# PidiBoy.net
KiCad netlist of a schematic drawn in EAGLE
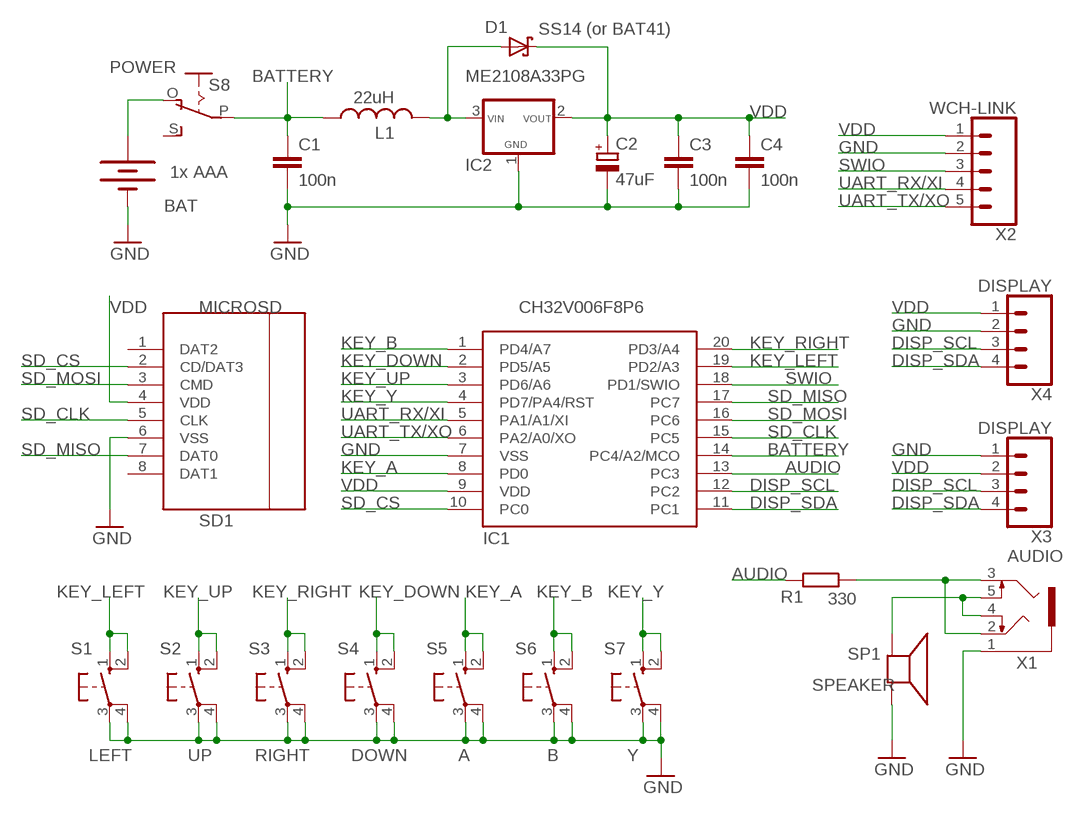
[diagram p0: schematic, sheet 1]

(export (version "E")
  (design (tool "Eeschema 10.0.6"))
  (components
    (comp (ref "BAT")
      (value "1x AAA")
      (footprint "eagle-import:BATTERY-AAA-KIT")
      (libsource (lib "eagle-import") (part "BATTERY-AAA_KIT"))
    )
    (comp (ref "C1")
      (value "100n")
      (footprint "eagle-import:C050-024X044")
      (libsource (lib "eagle-import") (part "C-EU050-024X044"))
    )
    (comp (ref "C2")
      (value "47uF")
      (footprint "eagle-import:E2-5")
      (libsource (lib "eagle-import") (part "CPOL-EUE2-5"))
    )
    (comp (ref "C3")
      (value "100n")
      (footprint "eagle-import:C050-024X044")
      (libsource (lib "eagle-import") (part "C-EU050-024X044"))
    )
    (comp (ref "C4")
      (value "100n")
      (footprint "eagle-import:C050-024X044")
      (libsource (lib "eagle-import") (part "C-EU050-024X044"))
    )
    (comp (ref "D1")
      (value "SS14 (or BAT41)")
      (footprint "eagle-import:DO35-7")
      (libsource (lib "eagle-import") (part "SCHOTTKY-DIODEDO35-7"))
    )
    (comp (ref "IC1")
      (value "CH32V006F8P6")
      (footprint "eagle-import:TSSOP20")
      (libsource (lib "eagle-import") (part "CH32V006F8P6"))
    )
    (comp (ref "IC2")
      (value "ME2108A33PG")
      (footprint "eagle-import:SOT89-R")
      (libsource (lib "eagle-import") (part "ME2108A33PG"))
    )
    (comp (ref "L1")
      (value "22uH")
      (footprint "eagle-import:POWER-CHOKE_WE-TPC")
      (libsource (lib "eagle-import") (part "L-USWE-TPC"))
    )
    (comp (ref "R1")
      (value "330")
      (footprint "eagle-import:0204_7")
      (libsource (lib "eagle-import") (part "R-EU_0204/7"))
    )
    (comp (ref "S1")
      (value "LEFT")
      (footprint "eagle-import:B3F-10XX")
      (fields (field (name "MPN") "B3F-1000"))
      (libsource (lib "eagle-import") (part "10-XX"))
    )
    (comp (ref "S2")
      (value "UP")
      (footprint "eagle-import:B3F-10XX")
      (fields (field (name "MPN") "B3F-1000"))
      (libsource (lib "eagle-import") (part "10-XX"))
    )
    (comp (ref "S3")
      (value "RIGHT")
      (footprint "eagle-import:B3F-10XX")
      (fields (field (name "MPN") "B3F-1000"))
      (libsource (lib "eagle-import") (part "10-XX"))
    )
    (comp (ref "S4")
      (value "DOWN")
      (footprint "eagle-import:B3F-10XX")
      (fields (field (name "MPN") "B3F-1000"))
      (libsource (lib "eagle-import") (part "10-XX"))
    )
    (comp (ref "S5")
      (value "A")
      (footprint "eagle-import:B3F-10XX")
      (fields (field (name "MPN") "B3F-1000"))
      (libsource (lib "eagle-import") (part "10-XX"))
    )
    (comp (ref "S6")
      (value "B")
      (footprint "eagle-import:B3F-10XX")
      (fields (field (name "MPN") "B3F-1000"))
      (libsource (lib "eagle-import") (part "10-XX"))
    )
    (comp (ref "S7")
      (value "Y")
      (footprint "eagle-import:B3F-10XX")
      (fields (field (name "MPN") "B3F-1000"))
      (libsource (lib "eagle-import") (part "10-XX"))
    )
    (comp (ref "S8")
      (value "POWER")
      (footprint "eagle-import:EG1218")
      (libsource (lib "eagle-import") (part "EG1218S"))
    )
    (comp (ref "SD1")
      (value "MICROSD")
      (footprint "eagle-import:MICROSD")
      (libsource (lib "eagle-import") (part "MICROSD"))
    )
    (comp (ref "SP1")
      (value "SPEAKER")
      (footprint "eagle-import:AL60P")
      (libsource (lib "eagle-import") (part "SPEAKER/AL60P"))
    )
    (comp (ref "X1")
      (value "AUDIO")
      (footprint "eagle-import:1503_09")
      (libsource (lib "eagle-import") (part "1503_09"))
    )
    (comp (ref "X2")
      (value "WCH-LINK")
      (footprint "eagle-import:1X05_LONGPADS")
      (libsource (lib "eagle-import") (part "CONN_05PTH_LONGPADS"))
    )
    (comp (ref "X3")
      (value "DISPLAY")
      (footprint "eagle-import:1X04")
      (libsource (lib "eagle-import") (part "CONN_04"))
    )
    (comp (ref "X4")
      (value "DISPLAY")
      (footprint "eagle-import:1X04")
      (libsource (lib "eagle-import") (part "CONN_04"))
    )
  )
  (nets
    (net (code "1") (name "/AUDIO") (class "Default")
      (node (ref "IC1") (pin "13") (pinfunction "PC3_13") (pintype "bidirectional"))
      (node (ref "R1") (pin "2") (pinfunction "2_2") (pintype "passive"))
    )
    (net (code "2") (name "/BATTERY") (class "Default")
      (node (ref "C1") (pin "1") (pinfunction "1_1") (pintype "passive"))
      (node (ref "IC1") (pin "14") (pinfunction "PC4/A2/MCO_14") (pintype "bidirectional"))
      (node (ref "L1") (pin "1") (pinfunction "1_1") (pintype "passive"))
      (node (ref "S8") (pin "P") (pinfunction "P_P") (pintype "passive"))
    )
    (net (code "3") (name "/DISP_SCL") (class "Default")
      (node (ref "IC1") (pin "12") (pinfunction "PC2_12") (pintype "bidirectional"))
      (node (ref "X3") (pin "3") (pinfunction "3_3") (pintype "passive"))
      (node (ref "X4") (pin "3") (pinfunction "3_3") (pintype "passive"))
    )
    (net (code "4") (name "/DISP_SDA") (class "Default")
      (node (ref "IC1") (pin "11") (pinfunction "PC1_11") (pintype "bidirectional"))
      (node (ref "X3") (pin "4") (pinfunction "4_4") (pintype "passive"))
      (node (ref "X4") (pin "4") (pinfunction "4_4") (pintype "passive"))
    )
    (net (code "5") (name "/KEY_A") (class "Default")
      (node (ref "IC1") (pin "8") (pinfunction "PD0_8") (pintype "bidirectional"))
      (node (ref "S5") (pin "1") (pinfunction "S_1") (pintype "passive"))
      (node (ref "S5") (pin "2") (pinfunction "S1_2") (pintype "passive"))
    )
    (net (code "6") (name "/KEY_B") (class "Default")
      (node (ref "IC1") (pin "1") (pinfunction "PD4/A7_1") (pintype "bidirectional"))
      (node (ref "S6") (pin "1") (pinfunction "S_1") (pintype "passive"))
      (node (ref "S6") (pin "2") (pinfunction "S1_2") (pintype "passive"))
    )
    (net (code "7") (name "/KEY_DOWN") (class "Default")
      (node (ref "IC1") (pin "2") (pinfunction "PD5/A5_2") (pintype "bidirectional"))
      (node (ref "S4") (pin "1") (pinfunction "S_1") (pintype "passive"))
      (node (ref "S4") (pin "2") (pinfunction "S1_2") (pintype "passive"))
    )
    (net (code "8") (name "/KEY_LEFT") (class "Default")
      (node (ref "IC1") (pin "19") (pinfunction "PD2/A3_19") (pintype "bidirectional"))
      (node (ref "S1") (pin "1") (pinfunction "S_1") (pintype "passive"))
      (node (ref "S1") (pin "2") (pinfunction "S1_2") (pintype "passive"))
    )
    (net (code "9") (name "/KEY_RIGHT") (class "Default")
      (node (ref "IC1") (pin "20") (pinfunction "PD3/A4_20") (pintype "bidirectional"))
      (node (ref "S3") (pin "1") (pinfunction "S_1") (pintype "passive"))
      (node (ref "S3") (pin "2") (pinfunction "S1_2") (pintype "passive"))
    )
    (net (code "10") (name "/KEY_UP") (class "Default")
      (node (ref "IC1") (pin "3") (pinfunction "PD6/A6_3") (pintype "bidirectional"))
      (node (ref "S2") (pin "1") (pinfunction "S_1") (pintype "passive"))
      (node (ref "S2") (pin "2") (pinfunction "S1_2") (pintype "passive"))
    )
    (net (code "11") (name "/KEY_Y") (class "Default")
      (node (ref "IC1") (pin "4") (pinfunction "PD7/PA4/RST_4") (pintype "bidirectional"))
      (node (ref "S7") (pin "1") (pinfunction "S_1") (pintype "passive"))
      (node (ref "S7") (pin "2") (pinfunction "S1_2") (pintype "passive"))
    )
    (net (code "12") (name "/SD_CLK") (class "Default")
      (node (ref "IC1") (pin "15") (pinfunction "PC5_15") (pintype "bidirectional"))
      (node (ref "SD1") (pin "5") (pinfunction "CLK_5") (pintype "bidirectional"))
    )
    (net (code "13") (name "/SD_CS") (class "Default")
      (node (ref "IC1") (pin "10") (pinfunction "PC0_10") (pintype "bidirectional"))
      (node (ref "SD1") (pin "2") (pinfunction "CD/DAT3_2") (pintype "bidirectional"))
    )
    (net (code "14") (name "/SD_MISO") (class "Default")
      (node (ref "IC1") (pin "17") (pinfunction "PC7_17") (pintype "bidirectional"))
      (node (ref "SD1") (pin "7") (pinfunction "DAT0_7") (pintype "bidirectional"))
    )
    (net (code "15") (name "/SD_MOSI") (class "Default")
      (node (ref "IC1") (pin "16") (pinfunction "PC6_16") (pintype "bidirectional"))
      (node (ref "SD1") (pin "3") (pinfunction "CMD_3") (pintype "bidirectional"))
    )
    (net (code "16") (name "/SWIO") (class "Default")
      (node (ref "IC1") (pin "18") (pinfunction "PD1/SWIO_18") (pintype "bidirectional"))
      (node (ref "X2") (pin "3") (pinfunction "3_3") (pintype "passive"))
    )
    (net (code "17") (name "/UART_RX{slash}XI") (class "Default")
      (node (ref "IC1") (pin "5") (pinfunction "PA1/A1/XI_5") (pintype "bidirectional"))
      (node (ref "X2") (pin "4") (pinfunction "4_4") (pintype "passive"))
    )
    (net (code "18") (name "/UART_TX{slash}XO") (class "Default")
      (node (ref "IC1") (pin "6") (pinfunction "PA2/A0/XO_6") (pintype "bidirectional"))
      (node (ref "X2") (pin "5") (pinfunction "5_5") (pintype "passive"))
    )
    (net (code "19") (name "/VDD") (class "Default")
      (node (ref "C2") (pin "+") (pinfunction "+_+") (pintype "passive"))
      (node (ref "C3") (pin "1") (pinfunction "1_1") (pintype "passive"))
      (node (ref "C4") (pin "1") (pinfunction "1_1") (pintype "passive"))
      (node (ref "D1") (pin "C") (pinfunction "C_C") (pintype "passive"))
      (node (ref "IC1") (pin "9") (pinfunction "VDD_9") (pintype "power_in"))
      (node (ref "IC2") (pin "2") (pinfunction "VOUT_2") (pintype "power_in"))
      (node (ref "SD1") (pin "4") (pinfunction "VDD_4") (pintype "bidirectional"))
      (node (ref "X2") (pin "1") (pinfunction "1_1") (pintype "passive"))
      (node (ref "X3") (pin "2") (pinfunction "2_2") (pintype "passive"))
      (node (ref "X4") (pin "1") (pinfunction "1_1") (pintype "passive"))
    )
    (net (code "20") (name "GND") (class "Default")
      (node (ref "BAT") (pin "GND@1") (pinfunction "-_GND@1") (pintype "power_in"))
      (node (ref "C1") (pin "2") (pinfunction "2_2") (pintype "passive"))
      (node (ref "C2") (pin "-") (pinfunction "-_-") (pintype "passive"))
      (node (ref "C3") (pin "2") (pinfunction "2_2") (pintype "passive"))
      (node (ref "C4") (pin "2") (pinfunction "2_2") (pintype "passive"))
      (node (ref "IC1") (pin "7") (pinfunction "VSS_7") (pintype "power_in"))
      (node (ref "IC2") (pin "1") (pinfunction "GND_1") (pintype "power_in"))
      (node (ref "S1") (pin "3") (pinfunction "P_3") (pintype "passive"))
      (node (ref "S1") (pin "4") (pinfunction "P1_4") (pintype "passive"))
      (node (ref "S2") (pin "3") (pinfunction "P_3") (pintype "passive"))
      (node (ref "S2") (pin "4") (pinfunction "P1_4") (pintype "passive"))
      (node (ref "S3") (pin "3") (pinfunction "P_3") (pintype "passive"))
      (node (ref "S3") (pin "4") (pinfunction "P1_4") (pintype "passive"))
      (node (ref "S4") (pin "3") (pinfunction "P_3") (pintype "passive"))
      (node (ref "S4") (pin "4") (pinfunction "P1_4") (pintype "passive"))
      (node (ref "S5") (pin "3") (pinfunction "P_3") (pintype "passive"))
      (node (ref "S5") (pin "4") (pinfunction "P1_4") (pintype "passive"))
      (node (ref "S6") (pin "3") (pinfunction "P_3") (pintype "passive"))
      (node (ref "S6") (pin "4") (pinfunction "P1_4") (pintype "passive"))
      (node (ref "S7") (pin "3") (pinfunction "P_3") (pintype "passive"))
      (node (ref "S7") (pin "4") (pinfunction "P1_4") (pintype "passive"))
      (node (ref "SD1") (pin "6") (pinfunction "VSS_6") (pintype "bidirectional"))
      (node (ref "SP1") (pin "2") (pinfunction "-_2") (pintype "passive"))
      (node (ref "X1") (pin "1") (pinfunction "1_1") (pintype "passive"))
      (node (ref "X2") (pin "2") (pinfunction "2_2") (pintype "passive"))
      (node (ref "X3") (pin "1") (pinfunction "1_1") (pintype "passive"))
      (node (ref "X4") (pin "2") (pinfunction "2_2") (pintype "passive"))
    )
    (net (code "21") (name "Net-(BAT-+)") (class "Default")
      (node (ref "BAT") (pin "PWR@1") (pinfunction "+_PWR@1") (pintype "power_in"))
      (node (ref "S8") (pin "O") (pinfunction "O_O") (pintype "passive"))
    )
    (net (code "22") (name "Net-(IC2-IN)") (class "Default")
      (node (ref "D1") (pin "A") (pinfunction "A_A") (pintype "passive"))
      (node (ref "IC2") (pin "3") (pinfunction "IN_3") (pintype "power_in"))
      (node (ref "L1") (pin "2") (pinfunction "2_2") (pintype "passive"))
    )
    (net (code "23") (name "Net-(R1-Pad1)") (class "Default")
      (node (ref "R1") (pin "1") (pinfunction "1_1") (pintype "passive"))
      (node (ref "X1") (pin "2") (pinfunction "2_2") (pintype "passive"))
      (node (ref "X1") (pin "3") (pinfunction "3_3") (pintype "passive"))
    )
    (net (code "24") (name "Net-(SP1-+)") (class "Default")
      (node (ref "SP1") (pin "1") (pinfunction "+_1") (pintype "passive"))
      (node (ref "X1") (pin "4") (pinfunction "4_4") (pintype "passive"))
      (node (ref "X1") (pin "5") (pinfunction "5_5") (pintype "passive"))
    )
    (net (code "25") (name "unconnected-(S8-PadS)") (class "Default")
      (node (ref "S8") (pin "S") (pinfunction "S_S") (pintype "passive"))
    )
    (net (code "26") (name "unconnected-(SD1-DAT1-Pad8)") (class "Default")
      (node (ref "SD1") (pin "8") (pinfunction "DAT1_8") (pintype "bidirectional"))
    )
    (net (code "27") (name "unconnected-(SD1-DAT2-Pad1)") (class "Default")
      (node (ref "SD1") (pin "1") (pinfunction "DAT2_1") (pintype "bidirectional"))
    )
  )
)
